# Board_Conns.net
KiCad netlist of a schematic drawn in Altium Designer
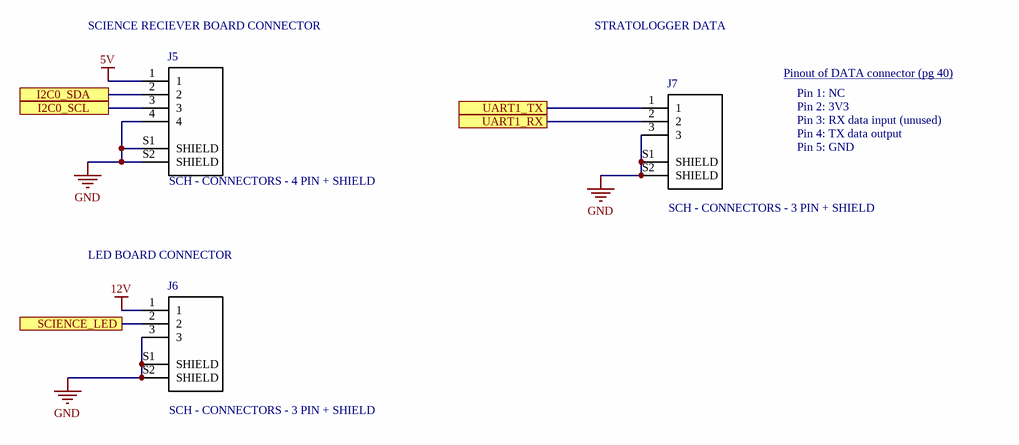
[diagram p0: Board_Conns.SchDoc]

(export (version "E")
  (design (tool "Eeschema 10.0.6"))
  (components
    (comp (ref "J5")
      (value "SCH - CONNECTORS - 4 PIN + SHIELD")
      (footprint "PCB - CONNECTOR - MOLEX - PICO-LOCK 5037630491")
      (description "Connector Header Surface Mount, Right Angle 4 position 0.039 _1.00mm_")
      (fields (field (name "MF") "Molex") (field (name "MP") "5037630491"))
      (libsource (lib "SCH - CONNECTORS - 4 PIN + SHIELD") (part "SCH - CONNECTORS - 4 PIN + SHIELD"))
    )
    (comp (ref "J6")
      (value "SCH - CONNECTORS - 3 PIN + SHIELD")
      (footprint "PCB - CONNECTOR - MOLEX - PICO-LOCK 5037630391")
      (description "Connector Header Surface Mount, Right Angle 4 position 0.039 _1.00mm_")
      (fields (field (name "MF") "Molex") (field (name "MP") "5037630491"))
      (libsource (lib "SCH - CONNECTORS - 3 PIN + SHIELD") (part "SCH - CONNECTORS - 3 PIN + SHIELD"))
    )
    (comp (ref "J7")
      (value "SCH - CONNECTORS - 3 PIN + SHIELD")
      (footprint "PCB - CONNECTOR - MOLEX - PICO-LOCK 5037630391")
      (description "Connector Header Surface Mount, Right Angle 4 position 0.039 _1.00mm_")
      (fields (field (name "MF") "Molex") (field (name "MP") "5037630491"))
      (libsource (lib "SCH - CONNECTORS - 3 PIN + SHIELD") (part "SCH - CONNECTORS - 3 PIN + SHIELD"))
    )
  )
  (nets
    (net (code "1") (name "/I2C0_SCL") (class "Default")
      (node (ref "J5") (pin "3") (pinfunction "3_3") (pintype "passive"))
    )
    (net (code "2") (name "/I2C0_SDA") (class "Default")
      (node (ref "J5") (pin "2") (pinfunction "2_2") (pintype "passive"))
    )
    (net (code "3") (name "/SCIENCE_LED") (class "Default")
      (node (ref "J6") (pin "2") (pinfunction "2_2") (pintype "passive"))
    )
    (net (code "4") (name "/UART1_RX") (class "Default")
      (node (ref "J7") (pin "2") (pinfunction "2_2") (pintype "passive"))
    )
    (net (code "5") (name "/UART1_TX") (class "Default")
      (node (ref "J7") (pin "1") (pinfunction "1_1") (pintype "passive"))
    )
    (net (code "6") (name "5V") (class "Default")
      (node (ref "J5") (pin "1") (pinfunction "1_1") (pintype "passive"))
    )
    (net (code "7") (name "12V") (class "Default")
      (node (ref "J6") (pin "1") (pinfunction "1_1") (pintype "passive"))
    )
    (net (code "8") (name "GND") (class "Default")
      (node (ref "J5") (pin "4") (pinfunction "4_4") (pintype "passive"))
      (node (ref "J5") (pin "S1") (pinfunction "SHIELD_S1") (pintype "passive"))
      (node (ref "J5") (pin "S2") (pinfunction "SHIELD_S2") (pintype "passive"))
      (node (ref "J6") (pin "3") (pinfunction "3_3") (pintype "passive"))
      (node (ref "J6") (pin "S1") (pinfunction "SHIELD_S1") (pintype "passive"))
      (node (ref "J6") (pin "S2") (pinfunction "SHIELD_S2") (pintype "passive"))
      (node (ref "J7") (pin "3") (pinfunction "3_3") (pintype "passive"))
      (node (ref "J7") (pin "S1") (pinfunction "SHIELD_S1") (pintype "passive"))
      (node (ref "J7") (pin "S2") (pinfunction "SHIELD_S2") (pintype "passive"))
    )
  )
)
